# eled02.net
KiCad netlist of a schematic drawn in EAGLE
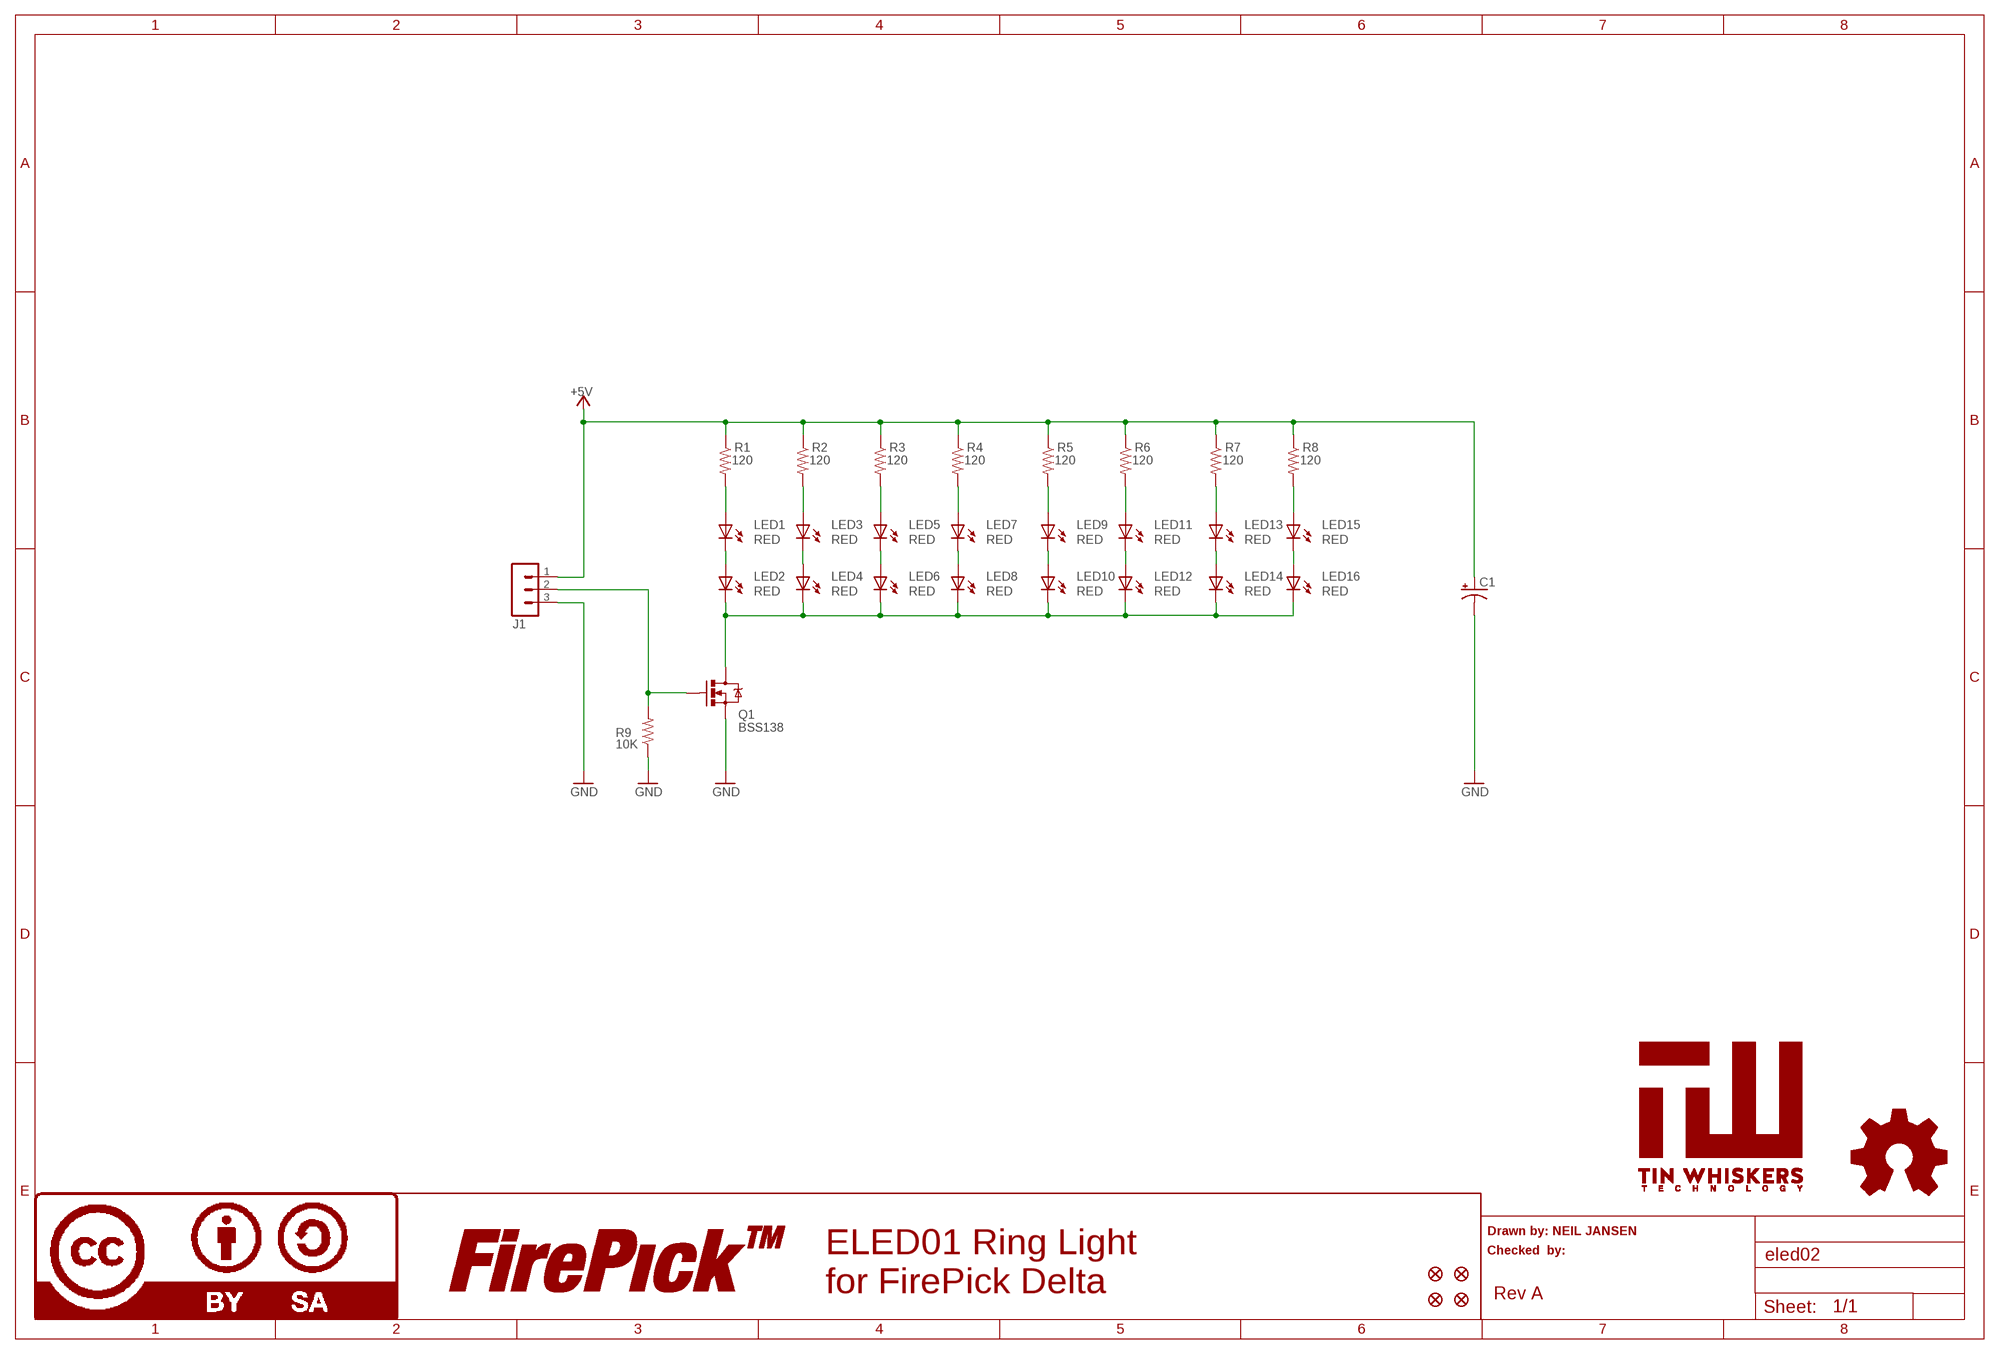
[diagram p0: schematic, sheet 1]

(export (version "E")
  (design (tool "Eeschema 10.0.6"))
  (components
    (comp (ref "C1")
      (value "10UF-25V-20%(PTH)")
      (footprint "eagle-import:CPOL-RADIAL-10UF-25V")
      (libsource (lib "eagle-import") (part "10UF-25V-20%(PTH)"))
    )
    (comp (ref "FID1")
      (value "FIDUCIAL1X2")
      (footprint "eagle-import:FIDUCIAL-1X2")
      (libsource (lib "eagle-import") (part "FIDUCIAL1X2"))
    )
    (comp (ref "FID2")
      (value "FIDUCIAL1X2")
      (footprint "eagle-import:FIDUCIAL-1X2")
      (libsource (lib "eagle-import") (part "FIDUCIAL1X2"))
    )
    (comp (ref "FID3")
      (value "FIDUCIAL1X2")
      (footprint "eagle-import:FIDUCIAL-1X2")
      (libsource (lib "eagle-import") (part "FIDUCIAL1X2"))
    )
    (comp (ref "FID4")
      (value "FIDUCIAL1X2")
      (footprint "eagle-import:FIDUCIAL-1X2")
      (libsource (lib "eagle-import") (part "FIDUCIAL1X2"))
    )
    (comp (ref "J1")
      (value "MA03-1")
      (footprint "eagle-import:MA03-1")
      (fields (field (name "PARTNO") "CONN-0.1-RA-1X3"))
      (libsource (lib "eagle-import") (part "MA03-1"))
    )
    (comp (ref "LED1")
      (value "RED")
      (footprint "eagle-import:LED-1206-NO_SILK")
      (fields (field (name "PARTNO") "LTST-C150CKT"))
      (libsource (lib "eagle-import") (part "LED1206-NS"))
    )
    (comp (ref "LED2")
      (value "RED")
      (footprint "eagle-import:LED-1206-NO_SILK")
      (fields (field (name "PARTNO") "LTST-C150CKT"))
      (libsource (lib "eagle-import") (part "LED1206-NS"))
    )
    (comp (ref "LED3")
      (value "RED")
      (footprint "eagle-import:LED-1206-NO_SILK")
      (fields (field (name "PARTNO") "LTST-C150CKT"))
      (libsource (lib "eagle-import") (part "LED1206-NS"))
    )
    (comp (ref "LED4")
      (value "RED")
      (footprint "eagle-import:LED-1206-NO_SILK")
      (fields (field (name "PARTNO") "LTST-C150CKT"))
      (libsource (lib "eagle-import") (part "LED1206-NS"))
    )
    (comp (ref "LED5")
      (value "RED")
      (footprint "eagle-import:LED-1206-NO_SILK")
      (fields (field (name "PARTNO") "LTST-C150CKT"))
      (libsource (lib "eagle-import") (part "LED1206-NS"))
    )
    (comp (ref "LED6")
      (value "RED")
      (footprint "eagle-import:LED-1206-NO_SILK")
      (fields (field (name "PARTNO") "LTST-C150CKT"))
      (libsource (lib "eagle-import") (part "LED1206-NS"))
    )
    (comp (ref "LED7")
      (value "RED")
      (footprint "eagle-import:LED-1206-NO_SILK")
      (fields (field (name "PARTNO") "LTST-C150CKT"))
      (libsource (lib "eagle-import") (part "LED1206-NS"))
    )
    (comp (ref "LED8")
      (value "RED")
      (footprint "eagle-import:LED-1206-NO_SILK")
      (fields (field (name "PARTNO") "LTST-C150CKT"))
      (libsource (lib "eagle-import") (part "LED1206-NS"))
    )
    (comp (ref "LED9")
      (value "RED")
      (footprint "eagle-import:LED-1206-NO_SILK")
      (fields (field (name "PARTNO") "LTST-C150CKT"))
      (libsource (lib "eagle-import") (part "LED1206-NS"))
    )
    (comp (ref "LED10")
      (value "RED")
      (footprint "eagle-import:LED-1206-NO_SILK")
      (fields (field (name "PARTNO") "LTST-C150CKT"))
      (libsource (lib "eagle-import") (part "LED1206-NS"))
    )
    (comp (ref "LED11")
      (value "RED")
      (footprint "eagle-import:LED-1206-NO_SILK")
      (fields (field (name "PARTNO") "LTST-C150CKT"))
      (libsource (lib "eagle-import") (part "LED1206-NS"))
    )
    (comp (ref "LED12")
      (value "RED")
      (footprint "eagle-import:LED-1206-NO_SILK")
      (fields (field (name "PARTNO") "LTST-C150CKT"))
      (libsource (lib "eagle-import") (part "LED1206-NS"))
    )
    (comp (ref "LED13")
      (value "RED")
      (footprint "eagle-import:LED-1206-NO_SILK")
      (fields (field (name "PARTNO") "LTST-C150CKT"))
      (libsource (lib "eagle-import") (part "LED1206-NS"))
    )
    (comp (ref "LED14")
      (value "RED")
      (footprint "eagle-import:LED-1206-NO_SILK")
      (fields (field (name "PARTNO") "LTST-C150CKT"))
      (libsource (lib "eagle-import") (part "LED1206-NS"))
    )
    (comp (ref "LED15")
      (value "RED")
      (footprint "eagle-import:LED-1206-NO_SILK")
      (fields (field (name "PARTNO") "LTST-C150CKT"))
      (libsource (lib "eagle-import") (part "LED1206-NS"))
    )
    (comp (ref "LED16")
      (value "RED")
      (footprint "eagle-import:LED-1206-NO_SILK")
      (fields (field (name "PARTNO") "LTST-C150CKT"))
      (libsource (lib "eagle-import") (part "LED1206-NS"))
    )
    (comp (ref "LOGO4")
      (value "LOGO-FIREPICKMEDIUM")
      (footprint "eagle-import:LOGO-FIREPICK-MEDIUM")
      (libsource (lib "eagle-import") (part "LOGO-FIREPICKMEDIUM"))
    )
    (comp (ref "LOGO5")
      (value "LOGO-OSHWSMALL")
      (footprint "eagle-import:LOGO-OSHW-SMALL")
      (libsource (lib "eagle-import") (part "LOGO-OSHWSMALL"))
    )
    (comp (ref "LOGO6")
      (value "LOGO-CC-BY-SAMEDIUM")
      (footprint "eagle-import:LOGO-CC-BY-SA-MEDIUM")
      (libsource (lib "eagle-import") (part "LOGO-CC-BY-SAMEDIUM"))
    )
    (comp (ref "Q1")
      (value "BSS138")
      (footprint "eagle-import:SOT23")
      (libsource (lib "eagle-import") (part "MOSFET-NCHANNELBSS138"))
    )
    (comp (ref "R1")
      (value "120")
      (footprint "eagle-import:0805")
      (fields (field (name "PARTNO") "RC0805FR-07120RL"))
      (libsource (lib "eagle-import") (part "RESISTOR0805-RES"))
    )
    (comp (ref "R2")
      (value "120")
      (footprint "eagle-import:0805")
      (fields (field (name "PARTNO") "RC0805FR-07120RL"))
      (libsource (lib "eagle-import") (part "RESISTOR0805-RES"))
    )
    (comp (ref "R3")
      (value "120")
      (footprint "eagle-import:0805")
      (fields (field (name "PARTNO") "RC0805FR-07120RL"))
      (libsource (lib "eagle-import") (part "RESISTOR0805-RES"))
    )
    (comp (ref "R4")
      (value "120")
      (footprint "eagle-import:0805")
      (fields (field (name "PARTNO") "RC0805FR-07120RL"))
      (libsource (lib "eagle-import") (part "RESISTOR0805-RES"))
    )
    (comp (ref "R5")
      (value "120")
      (footprint "eagle-import:0805")
      (fields (field (name "PARTNO") "RC0805FR-07120RL"))
      (libsource (lib "eagle-import") (part "RESISTOR0805-RES"))
    )
    (comp (ref "R6")
      (value "120")
      (footprint "eagle-import:0805")
      (fields (field (name "PARTNO") "RC0805FR-07120RL"))
      (libsource (lib "eagle-import") (part "RESISTOR0805-RES"))
    )
    (comp (ref "R7")
      (value "120")
      (footprint "eagle-import:0805")
      (fields (field (name "PARTNO") "RC0805FR-07120RL"))
      (libsource (lib "eagle-import") (part "RESISTOR0805-RES"))
    )
    (comp (ref "R8")
      (value "120")
      (footprint "eagle-import:0805")
      (fields (field (name "PARTNO") "RC0805FR-07120RL"))
      (libsource (lib "eagle-import") (part "RESISTOR0805-RES"))
    )
    (comp (ref "R9")
      (value "10K")
      (footprint "eagle-import:0805")
      (fields (field (name "PARTNO") "RC0805FR-0710KL"))
      (libsource (lib "eagle-import") (part "RESISTOR0805-RES"))
    )
    (comp (ref "U$1")
      (value "TIN-WHISKERSSMALL")
      (footprint "eagle-import:TIN-WHISKERS-SMALL")
      (libsource (lib "eagle-import") (part "TIN-WHISKERSSMALL"))
    )
  )
  (nets
    (net (code "1") (name "+5V") (class "Default")
      (node (ref "C1") (pin "1") (pinfunction "+_1") (pintype "passive"))
      (node (ref "J1") (pin "1") (pinfunction "1_1") (pintype "passive"))
      (node (ref "R1") (pin "1") (pinfunction "1_1") (pintype "passive"))
      (node (ref "R2") (pin "1") (pinfunction "1_1") (pintype "passive"))
      (node (ref "R3") (pin "1") (pinfunction "1_1") (pintype "passive"))
      (node (ref "R4") (pin "1") (pinfunction "1_1") (pintype "passive"))
      (node (ref "R5") (pin "1") (pinfunction "1_1") (pintype "passive"))
      (node (ref "R6") (pin "1") (pinfunction "1_1") (pintype "passive"))
      (node (ref "R7") (pin "1") (pinfunction "1_1") (pintype "passive"))
      (node (ref "R8") (pin "1") (pinfunction "1_1") (pintype "passive"))
    )
    (net (code "2") (name "GND") (class "Default")
      (node (ref "C1") (pin "2") (pinfunction "-_2") (pintype "passive"))
      (node (ref "J1") (pin "3") (pinfunction "3_3") (pintype "passive"))
      (node (ref "Q1") (pin "2") (pinfunction "S_2") (pintype "passive"))
      (node (ref "R9") (pin "1") (pinfunction "1_1") (pintype "passive"))
    )
    (net (code "3") (name "Net-(LED1-PadA)") (class "Default")
      (node (ref "LED1") (pin "A") (pinfunction "A_A") (pintype "passive"))
      (node (ref "R1") (pin "2") (pinfunction "2_2") (pintype "passive"))
    )
    (net (code "4") (name "Net-(LED1-PadC)") (class "Default")
      (node (ref "LED1") (pin "C") (pinfunction "C_C") (pintype "passive"))
      (node (ref "LED2") (pin "A") (pinfunction "A_A") (pintype "passive"))
    )
    (net (code "5") (name "Net-(LED3-PadA)") (class "Default")
      (node (ref "LED3") (pin "A") (pinfunction "A_A") (pintype "passive"))
      (node (ref "R2") (pin "2") (pinfunction "2_2") (pintype "passive"))
    )
    (net (code "6") (name "Net-(LED3-PadC)") (class "Default")
      (node (ref "LED3") (pin "C") (pinfunction "C_C") (pintype "passive"))
      (node (ref "LED4") (pin "A") (pinfunction "A_A") (pintype "passive"))
    )
    (net (code "7") (name "Net-(LED5-PadA)") (class "Default")
      (node (ref "LED5") (pin "A") (pinfunction "A_A") (pintype "passive"))
      (node (ref "R3") (pin "2") (pinfunction "2_2") (pintype "passive"))
    )
    (net (code "8") (name "Net-(LED5-PadC)") (class "Default")
      (node (ref "LED5") (pin "C") (pinfunction "C_C") (pintype "passive"))
      (node (ref "LED6") (pin "A") (pinfunction "A_A") (pintype "passive"))
    )
    (net (code "9") (name "Net-(LED7-PadA)") (class "Default")
      (node (ref "LED7") (pin "A") (pinfunction "A_A") (pintype "passive"))
      (node (ref "R4") (pin "2") (pinfunction "2_2") (pintype "passive"))
    )
    (net (code "10") (name "Net-(LED7-PadC)") (class "Default")
      (node (ref "LED7") (pin "C") (pinfunction "C_C") (pintype "passive"))
      (node (ref "LED8") (pin "A") (pinfunction "A_A") (pintype "passive"))
    )
    (net (code "11") (name "Net-(LED9-PadA)") (class "Default")
      (node (ref "LED9") (pin "A") (pinfunction "A_A") (pintype "passive"))
      (node (ref "R5") (pin "2") (pinfunction "2_2") (pintype "passive"))
    )
    (net (code "12") (name "Net-(LED10-PadA)") (class "Default")
      (node (ref "LED10") (pin "A") (pinfunction "A_A") (pintype "passive"))
      (node (ref "LED9") (pin "C") (pinfunction "C_C") (pintype "passive"))
    )
    (net (code "13") (name "Net-(LED11-PadA)") (class "Default")
      (node (ref "LED11") (pin "A") (pinfunction "A_A") (pintype "passive"))
      (node (ref "R6") (pin "2") (pinfunction "2_2") (pintype "passive"))
    )
    (net (code "14") (name "Net-(LED11-PadC)") (class "Default")
      (node (ref "LED11") (pin "C") (pinfunction "C_C") (pintype "passive"))
      (node (ref "LED12") (pin "A") (pinfunction "A_A") (pintype "passive"))
    )
    (net (code "15") (name "Net-(LED13-PadA)") (class "Default")
      (node (ref "LED13") (pin "A") (pinfunction "A_A") (pintype "passive"))
      (node (ref "R7") (pin "2") (pinfunction "2_2") (pintype "passive"))
    )
    (net (code "16") (name "Net-(LED13-PadC)") (class "Default")
      (node (ref "LED13") (pin "C") (pinfunction "C_C") (pintype "passive"))
      (node (ref "LED14") (pin "A") (pinfunction "A_A") (pintype "passive"))
    )
    (net (code "17") (name "Net-(LED15-PadA)") (class "Default")
      (node (ref "LED15") (pin "A") (pinfunction "A_A") (pintype "passive"))
      (node (ref "R8") (pin "2") (pinfunction "2_2") (pintype "passive"))
    )
    (net (code "18") (name "Net-(LED15-PadC)") (class "Default")
      (node (ref "LED15") (pin "C") (pinfunction "C_C") (pintype "passive"))
      (node (ref "LED16") (pin "A") (pinfunction "A_A") (pintype "passive"))
    )
    (net (code "19") (name "Net-(Q1-D)") (class "Default")
      (node (ref "LED10") (pin "C") (pinfunction "C_C") (pintype "passive"))
      (node (ref "LED12") (pin "C") (pinfunction "C_C") (pintype "passive"))
      (node (ref "LED14") (pin "C") (pinfunction "C_C") (pintype "passive"))
      (node (ref "LED16") (pin "C") (pinfunction "C_C") (pintype "passive"))
      (node (ref "LED2") (pin "C") (pinfunction "C_C") (pintype "passive"))
      (node (ref "LED4") (pin "C") (pinfunction "C_C") (pintype "passive"))
      (node (ref "LED6") (pin "C") (pinfunction "C_C") (pintype "passive"))
      (node (ref "LED8") (pin "C") (pinfunction "C_C") (pintype "passive"))
      (node (ref "Q1") (pin "3") (pinfunction "D_3") (pintype "passive"))
    )
    (net (code "20") (name "Net-(Q1-G)") (class "Default")
      (node (ref "J1") (pin "2") (pinfunction "2_2") (pintype "passive"))
      (node (ref "Q1") (pin "1") (pinfunction "G_1") (pintype "passive"))
      (node (ref "R9") (pin "2") (pinfunction "2_2") (pintype "passive"))
    )
  )
)
